# Communication.net
KiCad netlist of a schematic drawn in Altium Designer
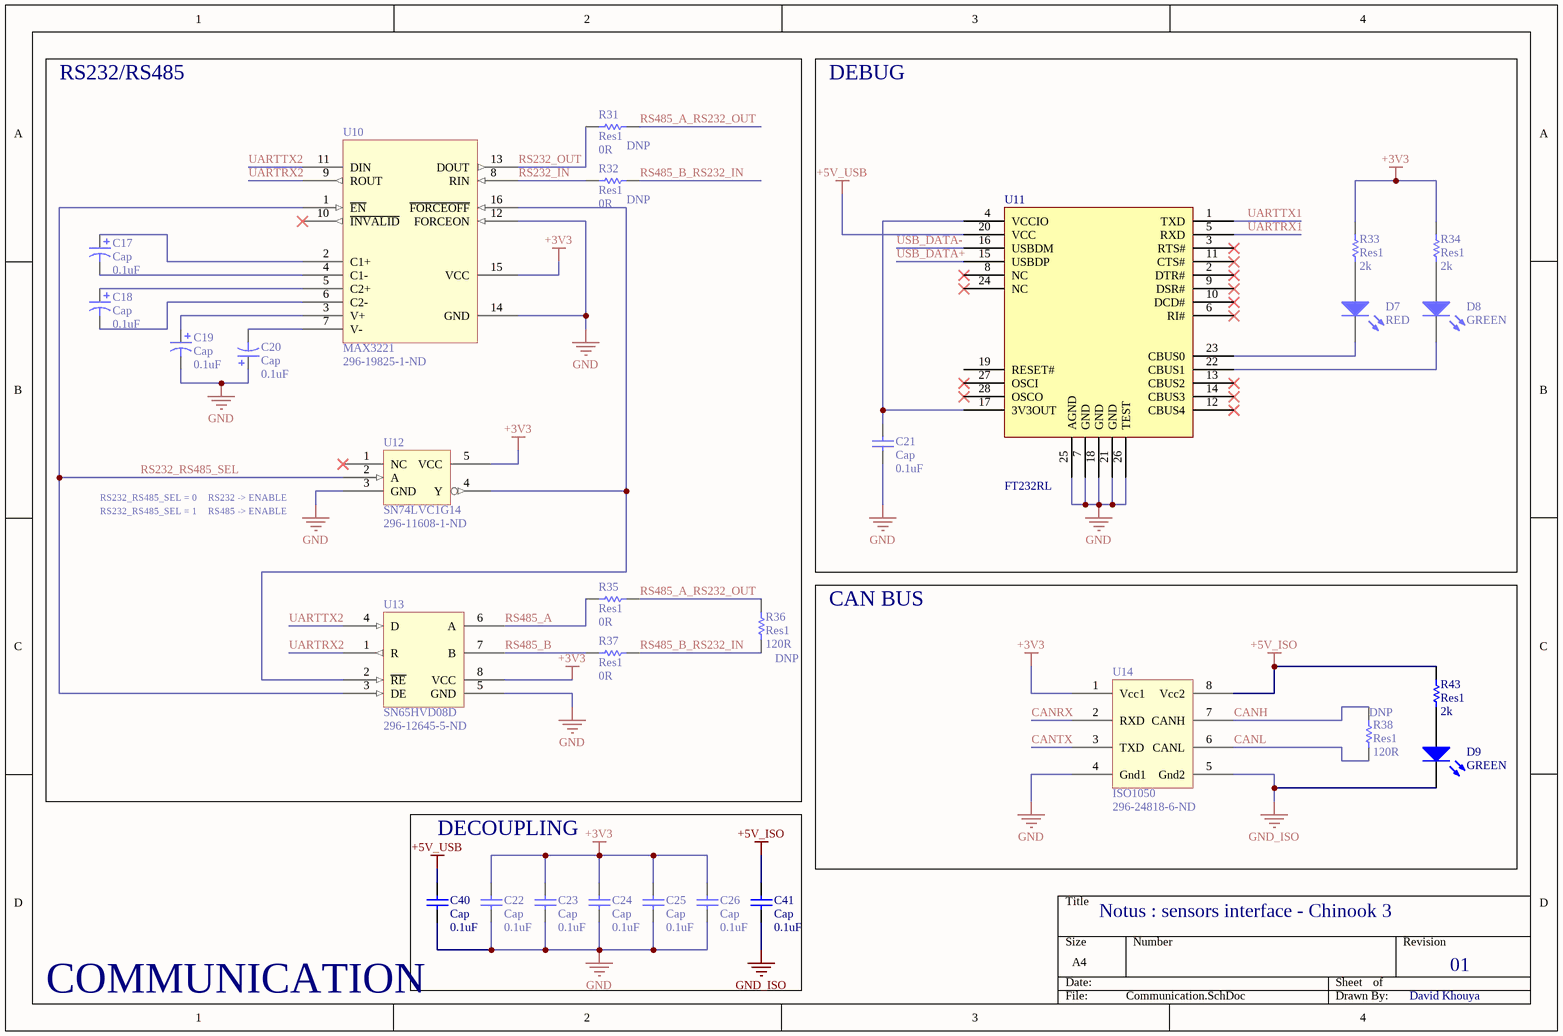
[diagram p0: Communication.SchDoc]

(export (version "E")
  (design (tool "Eeschema 10.0.6"))
  (components
    (comp (ref "C17")
      (value "Cap")
      (footprint "C0805")
      (description "Polarized Capacitor (Surface Mount)")
      (fields (field (name "ALTIUM_VALUE") "0.1uF") (field (name "PUBLISHER") "Altium Limited"))
      (libsource (lib "Miscellaneous Devices") (part "Cap Pol3"))
    )
    (comp (ref "C18")
      (value "Cap")
      (footprint "C0805")
      (description "Polarized Capacitor (Surface Mount)")
      (fields (field (name "ALTIUM_VALUE") "0.1uF") (field (name "PUBLISHER") "Altium Limited"))
      (libsource (lib "Miscellaneous Devices") (part "Cap Pol3"))
    )
    (comp (ref "C19")
      (value "Cap")
      (footprint "C0805")
      (description "Polarized Capacitor (Surface Mount)")
      (fields (field (name "ALTIUM_VALUE") "0.1uF") (field (name "PUBLISHER") "Altium Limited"))
      (libsource (lib "Miscellaneous Devices") (part "Cap Pol3"))
    )
    (comp (ref "C20")
      (value "Cap")
      (footprint "C0805")
      (description "Polarized Capacitor (Surface Mount)")
      (fields (field (name "ALTIUM_VALUE") "0.1uF") (field (name "PUBLISHER") "Altium Limited"))
      (libsource (lib "Miscellaneous Devices") (part "Cap Pol3"))
    )
    (comp (ref "C21")
      (value "Cap")
      (footprint "RESC2012N")
      (description "Capacitor")
      (fields (field (name "ALTIUM_VALUE") "0.1uF") (field (name "PUBLISHER") "Altium Limited"))
      (libsource (lib "Miscellaneous Devices") (part "Cap"))
    )
    (comp (ref "C22")
      (value "Cap")
      (footprint "RESC2012N")
      (description "Capacitor")
      (fields (field (name "ALTIUM_VALUE") "0.1uF") (field (name "PUBLISHER") "Altium Limited"))
      (libsource (lib "Miscellaneous Devices") (part "Cap"))
    )
    (comp (ref "C23")
      (value "Cap")
      (footprint "RESC2012N")
      (description "Capacitor")
      (fields (field (name "ALTIUM_VALUE") "0.1uF") (field (name "PUBLISHER") "Altium Limited"))
      (libsource (lib "Miscellaneous Devices") (part "Cap"))
    )
    (comp (ref "C24")
      (value "Cap")
      (footprint "RESC2012N")
      (description "Capacitor")
      (fields (field (name "ALTIUM_VALUE") "0.1uF") (field (name "PUBLISHER") "Altium Limited"))
      (libsource (lib "Miscellaneous Devices") (part "Cap"))
    )
    (comp (ref "C25")
      (value "Cap")
      (footprint "RESC2012N")
      (description "Capacitor")
      (fields (field (name "ALTIUM_VALUE") "0.1uF") (field (name "PUBLISHER") "Altium Limited"))
      (libsource (lib "Miscellaneous Devices") (part "Cap"))
    )
    (comp (ref "C26")
      (value "Cap")
      (footprint "RESC2012N")
      (description "Capacitor")
      (fields (field (name "ALTIUM_VALUE") "0.1uF") (field (name "PUBLISHER") "Altium Limited"))
      (libsource (lib "Miscellaneous Devices") (part "Cap"))
    )
    (comp (ref "C40")
      (value "Cap")
      (footprint "RESC2012N")
      (description "Capacitor")
      (fields (field (name "ALTIUM_VALUE") "0.1uF") (field (name "PUBLISHER") "Altium Limited"))
      (libsource (lib "Miscellaneous Devices") (part "Cap"))
    )
    (comp (ref "C41")
      (value "Cap")
      (footprint "RESC2012N")
      (description "Capacitor")
      (fields (field (name "ALTIUM_VALUE") "0.1uF") (field (name "PUBLISHER") "Altium Limited"))
      (libsource (lib "Miscellaneous Devices") (part "Cap"))
    )
    (comp (ref "D7")
      (value "RED")
      (footprint "0805_Diode")
      (description "Typical INFRARED GaAs LED")
      (fields (field (name "PUBLISHER") "Altium Limited"))
      (libsource (lib "Miscellaneous Devices") (part "LED0"))
    )
    (comp (ref "D8")
      (value "GREEN")
      (footprint "0805_Diode")
      (description "Typical INFRARED GaAs LED")
      (fields (field (name "PUBLISHER") "Altium Limited"))
      (libsource (lib "Miscellaneous Devices") (part "LED0"))
    )
    (comp (ref "D9")
      (value "GREEN")
      (footprint "0805_Diode")
      (description "Typical INFRARED GaAs LED")
      (fields (field (name "PUBLISHER") "Altium Limited"))
      (libsource (lib "Miscellaneous Devices") (part "LED0"))
    )
    (comp (ref "R31")
      (value "Res1")
      (footprint "RESC2012N")
      (description "Resistor")
      (fields
        (field (name "ALTIUM_VALUE") "0R")
        (field (name "DNP") "DNP")
        (field (name "PUBLISHER") "Altium Limited")
      )
      (libsource (lib "Miscellaneous Devices") (part "Res1"))
    )
    (comp (ref "R32")
      (value "Res1")
      (footprint "RESC2012N")
      (description "Resistor")
      (fields
        (field (name "ALTIUM_VALUE") "0R")
        (field (name "DNP") "DNP")
        (field (name "PUBLISHER") "Altium Limited")
      )
      (libsource (lib "Miscellaneous Devices") (part "Res1"))
    )
    (comp (ref "R33")
      (value "Res1")
      (footprint "RESC2012N")
      (description "Resistor")
      (fields (field (name "ALTIUM_VALUE") "2k") (field (name "PUBLISHER") "Altium Limited"))
      (libsource (lib "Miscellaneous Devices") (part "Res1"))
    )
    (comp (ref "R34")
      (value "Res1")
      (footprint "RESC2012N")
      (description "Resistor")
      (fields (field (name "ALTIUM_VALUE") "2k") (field (name "PUBLISHER") "Altium Limited"))
      (libsource (lib "Miscellaneous Devices") (part "Res1"))
    )
    (comp (ref "R35")
      (value "Res1")
      (footprint "RESC2012N")
      (description "Resistor")
      (fields (field (name "ALTIUM_VALUE") "0R") (field (name "PUBLISHER") "Altium Limited"))
      (libsource (lib "Miscellaneous Devices") (part "Res1"))
    )
    (comp (ref "R36")
      (value "Res1")
      (footprint "RESC2012N")
      (description "Resistor")
      (fields
        (field (name "ALTIUM_VALUE") "120R")
        (field (name "DNP") "DNP")
        (field (name "PUBLISHER") "Altium Limited")
      )
      (libsource (lib "Miscellaneous Devices") (part "Res1"))
    )
    (comp (ref "R37")
      (value "Res1")
      (footprint "RESC2012N")
      (description "Resistor")
      (fields (field (name "ALTIUM_VALUE") "0R") (field (name "PUBLISHER") "Altium Limited"))
      (libsource (lib "Miscellaneous Devices") (part "Res1"))
    )
    (comp (ref "R38")
      (value "Res1")
      (footprint "RESC2012N")
      (description "Resistor")
      (fields
        (field (name "ALTIUM_VALUE") "120R")
        (field (name "DNP") "DNP")
        (field (name "PUBLISHER") "Altium Limited")
      )
      (libsource (lib "Miscellaneous Devices") (part "Res1"))
    )
    (comp (ref "R43")
      (value "Res1")
      (footprint "RESC2012N")
      (description "Resistor")
      (fields (field (name "ALTIUM_VALUE") "2k") (field (name "PUBLISHER") "Altium Limited"))
      (libsource (lib "Miscellaneous Devices") (part "Res1"))
    )
    (comp (ref "U10")
      (value "MAX3221")
      (footprint "SSOP16_M")
      (description "RS232 to TTL")
      (fields (field (name "SUPPLIER PART NUMBER 1") "296-19825-1-ND"))
      (libsource (lib "dkhouya") (part "MAX3221"))
    )
    (comp (ref "U11")
      (value "FT232RL")
      (footprint "ssop-28")
      (description "USB UART IC")
      (libsource (lib "dkhouya") (part "FT232RL"))
    )
    (comp (ref "U12")
      (value "SN74LVC1G14")
      (footprint "SOT23-5AM")
      (description "Inverter Gate")
      (fields (field (name "SUPPLIER PART NUMBER 1") "296-11608-1-ND"))
      (libsource (lib "dkhouya") (part "SN74LVC1G14"))
    )
    (comp (ref "U13")
      (value "SN65HVD08D")
      (footprint "8SOIC-2")
      (description "RS485 to TTL")
      (fields (field (name "SUPPLIER PART NUMBER 1") "296-12645-5-ND"))
      (libsource (lib "dkhouya") (part "SN65HVD08D"))
    )
    (comp (ref "U14")
      (value "ISO1050")
      (footprint "SOP-8")
      (description "ISOLATED CAN TRANSCEIVER")
      (fields (field (name "SUPPLIER PART NUMBER 1") "296-24818-6-ND"))
      (libsource (lib "dkhouya") (part "ISO1050"))
    )
  )
  (nets
    (net (code "1") (name "+3V3") (class "Default")
      (node (ref "C22") (pin "2") (pinfunction "2_2") (pintype "passive"))
      (node (ref "C23") (pin "2") (pinfunction "2_2") (pintype "passive"))
      (node (ref "C24") (pin "2") (pinfunction "2_2") (pintype "passive"))
      (node (ref "C25") (pin "2") (pinfunction "2_2") (pintype "passive"))
      (node (ref "C26") (pin "2") (pinfunction "2_2") (pintype "passive"))
      (node (ref "R33") (pin "1") (pinfunction "1_1") (pintype "passive"))
      (node (ref "R34") (pin "1") (pinfunction "1_1") (pintype "passive"))
      (node (ref "U10") (pin "15") (pinfunction "VCC_15") (pintype "power_in"))
      (node (ref "U12") (pin "5") (pinfunction "VCC_5") (pintype "power_in"))
      (node (ref "U13") (pin "8") (pinfunction "VCC_8") (pintype "power_in"))
      (node (ref "U14") (pin "1") (pinfunction "Vcc1_1") (pintype "power_in"))
    )
    (net (code "2") (name "+5V_ISO") (class "Default")
      (node (ref "C41") (pin "2") (pinfunction "2_2") (pintype "passive"))
      (node (ref "R43") (pin "1") (pinfunction "1_1") (pintype "passive"))
      (node (ref "U14") (pin "8") (pinfunction "Vcc2_8") (pintype "passive"))
    )
    (net (code "3") (name "+5V_USB") (class "Default")
      (node (ref "C40") (pin "2") (pinfunction "2_2") (pintype "passive"))
      (node (ref "U11") (pin "20") (pinfunction "VCC_20") (pintype "passive"))
    )
    (net (code "4") (name "/CANH") (class "Default")
      (node (ref "R38") (pin "1") (pinfunction "1_1") (pintype "passive"))
      (node (ref "U14") (pin "7") (pinfunction "CANH_7") (pintype "passive"))
    )
    (net (code "5") (name "/CANL") (class "Default")
      (node (ref "R38") (pin "2") (pinfunction "2_2") (pintype "passive"))
      (node (ref "U14") (pin "6") (pinfunction "CANL_6") (pintype "passive"))
    )
    (net (code "6") (name "/CANRX") (class "Default")
      (node (ref "U14") (pin "2") (pinfunction "RXD_2") (pintype "passive"))
    )
    (net (code "7") (name "/CANTX") (class "Default")
      (node (ref "U14") (pin "3") (pinfunction "TXD_3") (pintype "passive"))
    )
    (net (code "8") (name "/RS232_IN") (class "Default")
      (node (ref "R32") (pin "1") (pinfunction "1_1") (pintype "passive"))
      (node (ref "U10") (pin "8") (pinfunction "RIN_8") (pintype "input"))
    )
    (net (code "9") (name "/RS232_OUT") (class "Default")
      (node (ref "R31") (pin "1") (pinfunction "1_1") (pintype "passive"))
      (node (ref "U10") (pin "13") (pinfunction "DOUT_13") (pintype "output"))
    )
    (net (code "10") (name "/RS232_RS485_SEL") (class "Default")
      (node (ref "U10") (pin "1") (pinfunction "~{EN}_1") (pintype "input"))
      (node (ref "U12") (pin "2") (pinfunction "A_2") (pintype "input"))
      (node (ref "U13") (pin "3") (pinfunction "DE_3") (pintype "input"))
    )
    (net (code "11") (name "/RS485_A") (class "Default")
      (node (ref "R35") (pin "1") (pinfunction "1_1") (pintype "passive"))
      (node (ref "U13") (pin "6") (pinfunction "A_6") (pintype "passive"))
    )
    (net (code "12") (name "/RS485_A_RS232_OUT") (class "Default")
      (node (ref "R31") (pin "2") (pinfunction "2_2") (pintype "passive"))
      (node (ref "R35") (pin "2") (pinfunction "2_2") (pintype "passive"))
      (node (ref "R36") (pin "2") (pinfunction "2_2") (pintype "passive"))
    )
    (net (code "13") (name "/RS485_B") (class "Default")
      (node (ref "R37") (pin "1") (pinfunction "1_1") (pintype "passive"))
      (node (ref "U13") (pin "7") (pinfunction "B_7") (pintype "passive"))
    )
    (net (code "14") (name "/RS485_B_RS232_IN") (class "Default")
      (node (ref "R32") (pin "2") (pinfunction "2_2") (pintype "passive"))
      (node (ref "R36") (pin "1") (pinfunction "1_1") (pintype "passive"))
      (node (ref "R37") (pin "2") (pinfunction "2_2") (pintype "passive"))
    )
    (net (code "15") (name "/UARTRX1") (class "Default")
      (node (ref "U11") (pin "5") (pinfunction "RXD_5") (pintype "passive"))
    )
    (net (code "16") (name "/UARTRX2") (class "Default")
      (node (ref "U10") (pin "9") (pinfunction "ROUT_9") (pintype "output"))
      (node (ref "U13") (pin "1") (pinfunction "R_1") (pintype "output"))
    )
    (net (code "17") (name "/UARTTX1") (class "Default")
      (node (ref "U11") (pin "1") (pinfunction "TXD_1") (pintype "passive"))
    )
    (net (code "18") (name "/UARTTX2") (class "Default")
      (node (ref "U10") (pin "11") (pinfunction "DIN_11") (pintype "passive"))
      (node (ref "U13") (pin "4") (pinfunction "D_4") (pintype "input"))
    )
    (net (code "19") (name "/USB_DATA+") (class "Default")
      (node (ref "U11") (pin "15") (pinfunction "USBDP_15") (pintype "passive"))
    )
    (net (code "20") (name "/USB_DATA-") (class "Default")
      (node (ref "U11") (pin "16") (pinfunction "USBDM_16") (pintype "passive"))
    )
    (net (code "21") (name "GND") (class "Default")
      (node (ref "C19") (pin "2") (pinfunction "2_2") (pintype "passive"))
      (node (ref "C20") (pin "1") (pinfunction "1_1") (pintype "passive"))
      (node (ref "C21") (pin "1") (pinfunction "1_1") (pintype "passive"))
      (node (ref "C22") (pin "1") (pinfunction "1_1") (pintype "passive"))
      (node (ref "C23") (pin "1") (pinfunction "1_1") (pintype "passive"))
      (node (ref "C24") (pin "1") (pinfunction "1_1") (pintype "passive"))
      (node (ref "C25") (pin "1") (pinfunction "1_1") (pintype "passive"))
      (node (ref "C26") (pin "1") (pinfunction "1_1") (pintype "passive"))
      (node (ref "C40") (pin "1") (pinfunction "1_1") (pintype "passive"))
      (node (ref "U10") (pin "12") (pinfunction "FORCEON_12") (pintype "input"))
      (node (ref "U10") (pin "14") (pinfunction "GND_14") (pintype "power_in"))
      (node (ref "U11") (pin "18") (pinfunction "GND_18") (pintype "passive"))
      (node (ref "U11") (pin "21") (pinfunction "GND_21") (pintype "passive"))
      (node (ref "U11") (pin "25") (pinfunction "AGND_25") (pintype "passive"))
      (node (ref "U11") (pin "26") (pinfunction "TEST_26") (pintype "passive"))
      (node (ref "U11") (pin "7") (pinfunction "GND_7") (pintype "passive"))
      (node (ref "U12") (pin "3") (pinfunction "GND_3") (pintype "power_in"))
      (node (ref "U13") (pin "5") (pinfunction "GND_5") (pintype "power_in"))
      (node (ref "U14") (pin "4") (pinfunction "Gnd1_4") (pintype "passive"))
    )
    (net (code "22") (name "GND_ISO") (class "Default")
      (node (ref "C41") (pin "1") (pinfunction "1_1") (pintype "passive"))
      (node (ref "D9") (pin "2") (pinfunction "K_2") (pintype "passive"))
      (node (ref "U14") (pin "5") (pinfunction "Gnd2_5") (pintype "passive"))
    )
    (net (code "23") (name "Net-(D7-A)") (class "Default")
      (node (ref "D7") (pin "1") (pinfunction "A_1") (pintype "passive"))
      (node (ref "R33") (pin "2") (pinfunction "2_2") (pintype "passive"))
    )
    (net (code "24") (name "Net-(D7-K)") (class "Default")
      (node (ref "D7") (pin "2") (pinfunction "K_2") (pintype "passive"))
      (node (ref "U11") (pin "23") (pinfunction "CBUS0_23") (pintype "passive"))
    )
    (net (code "25") (name "Net-(D8-A)") (class "Default")
      (node (ref "D8") (pin "1") (pinfunction "A_1") (pintype "passive"))
      (node (ref "R34") (pin "2") (pinfunction "2_2") (pintype "passive"))
    )
    (net (code "26") (name "Net-(D8-K)") (class "Default")
      (node (ref "D8") (pin "2") (pinfunction "K_2") (pintype "passive"))
      (node (ref "U11") (pin "22") (pinfunction "CBUS1_22") (pintype "passive"))
    )
    (net (code "27") (name "Net-(D9-A)") (class "Default")
      (node (ref "D9") (pin "1") (pinfunction "A_1") (pintype "passive"))
      (node (ref "R43") (pin "2") (pinfunction "2_2") (pintype "passive"))
    )
    (net (code "28") (name "Net-(U10-C1+)") (class "Default")
      (node (ref "C17") (pin "1") (pinfunction "1_1") (pintype "passive"))
      (node (ref "U10") (pin "2") (pinfunction "C1+_2") (pintype "passive"))
    )
    (net (code "29") (name "Net-(U10-C1-)") (class "Default")
      (node (ref "C17") (pin "2") (pinfunction "2_2") (pintype "passive"))
      (node (ref "U10") (pin "4") (pinfunction "C1-_4") (pintype "passive"))
    )
    (net (code "30") (name "Net-(U10-C2+)") (class "Default")
      (node (ref "C18") (pin "1") (pinfunction "1_1") (pintype "passive"))
      (node (ref "U10") (pin "5") (pinfunction "C2+_5") (pintype "passive"))
    )
    (net (code "31") (name "Net-(U10-C2-)") (class "Default")
      (node (ref "C18") (pin "2") (pinfunction "2_2") (pintype "passive"))
      (node (ref "U10") (pin "6") (pinfunction "C2-_6") (pintype "passive"))
    )
    (net (code "32") (name "Net-(U10-V+)") (class "Default")
      (node (ref "C19") (pin "1") (pinfunction "1_1") (pintype "passive"))
      (node (ref "U10") (pin "3") (pinfunction "V+_3") (pintype "passive"))
    )
    (net (code "33") (name "Net-(U10-V-)") (class "Default")
      (node (ref "C20") (pin "2") (pinfunction "2_2") (pintype "passive"))
      (node (ref "U10") (pin "7") (pinfunction "V-_7") (pintype "passive"))
    )
    (net (code "34") (name "Net-(U10-~{FORCEOFF})") (class "Default")
      (node (ref "U10") (pin "16") (pinfunction "~{FORCEOFF}_16") (pintype "input"))
      (node (ref "U12") (pin "4") (pinfunction "Y_4") (pintype "output"))
      (node (ref "U13") (pin "2") (pinfunction "~{RE}_2") (pintype "input"))
    )
    (net (code "35") (name "Net-(U11-3V3OUT)") (class "Default")
      (node (ref "C21") (pin "2") (pinfunction "2_2") (pintype "passive"))
      (node (ref "U11") (pin "17") (pinfunction "3V3OUT_17") (pintype "passive"))
      (node (ref "U11") (pin "4") (pinfunction "VCCIO_4") (pintype "passive"))
    )
    (net (code "36") (name "unconnected-(U10-~{INVALID}-Pad10)") (class "Default")
      (node (ref "U10") (pin "10") (pinfunction "~{INVALID}_10") (pintype "output+no_connect"))
    )
    (net (code "37") (name "unconnected-(U11-CBUS2-Pad13)") (class "Default")
      (node (ref "U11") (pin "13") (pinfunction "CBUS2_13") (pintype "passive+no_connect"))
    )
    (net (code "38") (name "unconnected-(U11-CBUS3-Pad14)") (class "Default")
      (node (ref "U11") (pin "14") (pinfunction "CBUS3_14") (pintype "passive+no_connect"))
    )
    (net (code "39") (name "unconnected-(U11-CBUS4-Pad12)") (class "Default")
      (node (ref "U11") (pin "12") (pinfunction "CBUS4_12") (pintype "passive+no_connect"))
    )
    (net (code "40") (name "unconnected-(U11-CTS#-Pad11)") (class "Default")
      (node (ref "U11") (pin "11") (pinfunction "CTS#_11") (pintype "passive+no_connect"))
    )
    (net (code "41") (name "unconnected-(U11-DCD#-Pad10)") (class "Default")
      (node (ref "U11") (pin "10") (pinfunction "DCD#_10") (pintype "passive+no_connect"))
    )
    (net (code "42") (name "unconnected-(U11-DSR#-Pad9)") (class "Default")
      (node (ref "U11") (pin "9") (pinfunction "DSR#_9") (pintype "passive+no_connect"))
    )
    (net (code "43") (name "unconnected-(U11-DTR#-Pad2)") (class "Default")
      (node (ref "U11") (pin "2") (pinfunction "DTR#_2") (pintype "passive+no_connect"))
    )
    (net (code "44") (name "unconnected-(U11-NC-Pad8)") (class "Default")
      (node (ref "U11") (pin "8") (pinfunction "NC_8") (pintype "passive+no_connect"))
    )
    (net (code "45") (name "unconnected-(U11-NC-Pad24)") (class "Default")
      (node (ref "U11") (pin "24") (pinfunction "NC_24") (pintype "passive+no_connect"))
    )
    (net (code "46") (name "unconnected-(U11-OSCI-Pad27)") (class "Default")
      (node (ref "U11") (pin "27") (pinfunction "OSCI_27") (pintype "passive+no_connect"))
    )
    (net (code "47") (name "unconnected-(U11-OSCO-Pad28)") (class "Default")
      (node (ref "U11") (pin "28") (pinfunction "OSCO_28") (pintype "passive+no_connect"))
    )
    (net (code "48") (name "unconnected-(U11-RESET#-Pad19)") (class "Default")
      (node (ref "U11") (pin "19") (pinfunction "RESET#_19") (pintype "passive"))
    )
    (net (code "49") (name "unconnected-(U11-RI#-Pad6)") (class "Default")
      (node (ref "U11") (pin "6") (pinfunction "RI#_6") (pintype "passive+no_connect"))
    )
    (net (code "50") (name "unconnected-(U11-RTS#-Pad3)") (class "Default")
      (node (ref "U11") (pin "3") (pinfunction "RTS#_3") (pintype "passive+no_connect"))
    )
    (net (code "51") (name "unconnected-(U12-NC-Pad1)") (class "Default")
      (node (ref "U12") (pin "1") (pinfunction "NC_1") (pintype "passive+no_connect"))
    )
  )
)
